# MAGI_sOLED.net
KiCad netlist of a schematic drawn in Altium Designer
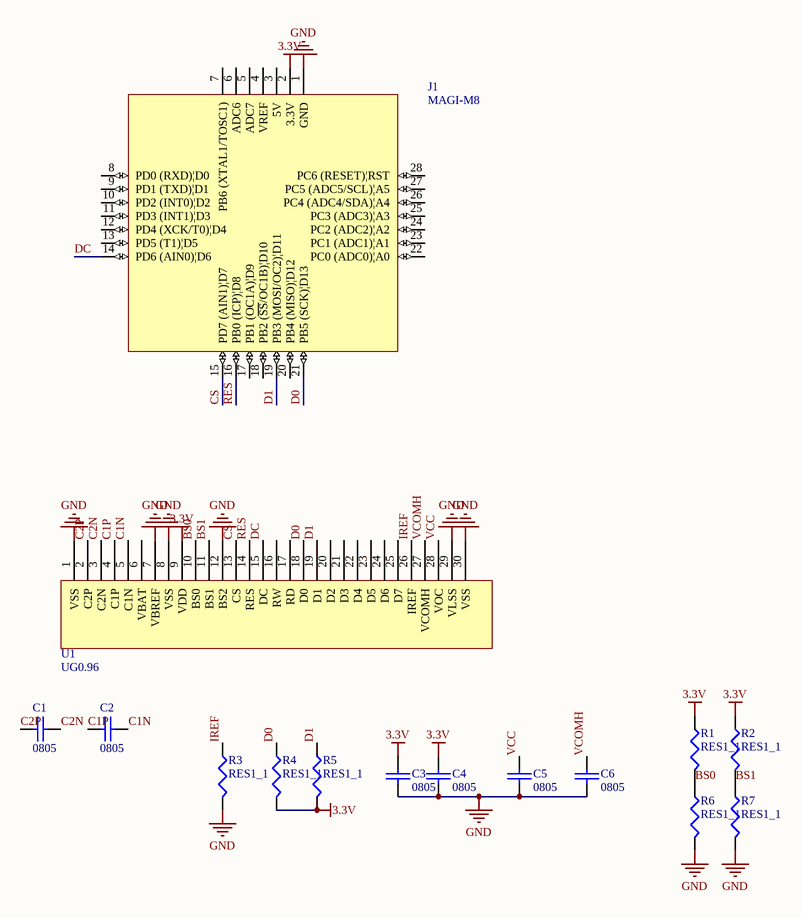
[diagram p0: MAGI'sOLED.SchDoc]

(export (version "E")
  (design (tool "Eeschema 10.0.6"))
  (components
    (comp (ref "C1")
      (value "0805")
      (footprint "6-0805_N")
      (description "Capacitor")
      (libsource (lib "电容器") (part "CAP_1"))
    )
    (comp (ref "C2")
      (value "0805")
      (footprint "6-0805_N")
      (description "Capacitor")
      (libsource (lib "电容器") (part "CAP_1"))
    )
    (comp (ref "C3")
      (value "0805")
      (footprint "6-0805_N")
      (description "Capacitor")
      (libsource (lib "电容器") (part "CAP_1"))
    )
    (comp (ref "C4")
      (value "0805")
      (footprint "6-0805_N")
      (description "Capacitor")
      (libsource (lib "电容器") (part "CAP_1"))
    )
    (comp (ref "C5")
      (value "0805")
      (footprint "6-0805_N")
      (description "Capacitor")
      (libsource (lib "电容器") (part "CAP_1"))
    )
    (comp (ref "C6")
      (value "0805")
      (footprint "6-0805_N")
      (description "Capacitor")
      (libsource (lib "电容器") (part "CAP_1"))
    )
    (comp (ref "J1") (value "MAGI-M8") (footprint "MAGI-M8") (libsource (lib "MAGI-M8") (part "MAGI-M8")))
    (comp (ref "R1") (value "RES1_1") (footprint "1608[0603]") (libsource (lib "电阻器") (part "RES1_1")))
    (comp (ref "R2") (value "RES1_1") (footprint "1608[0603]") (libsource (lib "电阻器") (part "RES1_1")))
    (comp (ref "R3") (value "RES1_1") (footprint "6-0805_n") (libsource (lib "电阻器") (part "RES1_1")))
    (comp (ref "R4") (value "RES1_1") (footprint "6-0805_n") (libsource (lib "电阻器") (part "RES1_1")))
    (comp (ref "R5") (value "RES1_1") (footprint "6-0805_n") (libsource (lib "电阻器") (part "RES1_1")))
    (comp (ref "R6") (value "RES1_1") (footprint "1608[0603]") (libsource (lib "电阻器") (part "RES1_1")))
    (comp (ref "R7") (value "RES1_1") (footprint "1608[0603]") (libsource (lib "电阻器") (part "RES1_1")))
    (comp (ref "U1") (value "UG0.96") (footprint "UG0.96") (libsource (lib "OLED") (part "UG0.96")))
  )
  (nets
    (net (code "1") (name "/BS0") (class "Default")
      (node (ref "R1") (pin "2") (pinfunction "2_2") (pintype "passive"))
      (node (ref "R6") (pin "1") (pinfunction "1_1") (pintype "passive"))
      (node (ref "U1") (pin "10") (pinfunction "BS0_10") (pintype "passive"))
    )
    (net (code "2") (name "/BS1") (class "Default")
      (node (ref "R2") (pin "2") (pinfunction "2_2") (pintype "passive"))
      (node (ref "R7") (pin "1") (pinfunction "1_1") (pintype "passive"))
      (node (ref "U1") (pin "11") (pinfunction "BS1_11") (pintype "passive"))
    )
    (net (code "3") (name "/C1N") (class "Default")
      (node (ref "C2") (pin "2") (pinfunction "2_2") (pintype "passive"))
      (node (ref "U1") (pin "5") (pinfunction "C1N_5") (pintype "passive"))
    )
    (net (code "4") (name "/C1P") (class "Default")
      (node (ref "C2") (pin "1") (pinfunction "1_1") (pintype "passive"))
      (node (ref "U1") (pin "4") (pinfunction "C1P_4") (pintype "passive"))
    )
    (net (code "5") (name "/C2N") (class "Default")
      (node (ref "C1") (pin "2") (pinfunction "2_2") (pintype "passive"))
      (node (ref "U1") (pin "3") (pinfunction "C2N_3") (pintype "passive"))
    )
    (net (code "6") (name "/C2P") (class "Default")
      (node (ref "C1") (pin "1") (pinfunction "1_1") (pintype "passive"))
      (node (ref "U1") (pin "2") (pinfunction "C2P_2") (pintype "passive"))
    )
    (net (code "7") (name "/CS") (class "Default")
      (node (ref "J1") (pin "15") (pinfunction "PD7_(AIN1)¦D7_15") (pintype "bidirectional"))
      (node (ref "U1") (pin "13") (pinfunction "CS_13") (pintype "passive"))
    )
    (net (code "8") (name "/D0") (class "Default")
      (node (ref "J1") (pin "21") (pinfunction "PB5_(SCK)¦D13_21") (pintype "bidirectional"))
      (node (ref "R4") (pin "1") (pinfunction "1_1") (pintype "passive"))
      (node (ref "U1") (pin "18") (pinfunction "D0_18") (pintype "passive"))
    )
    (net (code "9") (name "/D1") (class "Default")
      (node (ref "J1") (pin "19") (pinfunction "PB3_(MOSI/OC2)¦D11_19") (pintype "bidirectional"))
      (node (ref "R5") (pin "1") (pinfunction "1_1") (pintype "passive"))
      (node (ref "U1") (pin "19") (pinfunction "D1_19") (pintype "passive"))
    )
    (net (code "10") (name "/DC") (class "Default")
      (node (ref "J1") (pin "14") (pinfunction "PD6_(AIN0)¦D6_14") (pintype "bidirectional"))
      (node (ref "U1") (pin "15") (pinfunction "DC_15") (pintype "passive"))
    )
    (net (code "11") (name "/IREF") (class "Default")
      (node (ref "R3") (pin "1") (pinfunction "1_1") (pintype "passive"))
      (node (ref "U1") (pin "26") (pinfunction "IREF_26") (pintype "passive"))
    )
    (net (code "12") (name "/RES") (class "Default")
      (node (ref "J1") (pin "16") (pinfunction "PB0_(ICP)¦D8_16") (pintype "bidirectional"))
      (node (ref "U1") (pin "14") (pinfunction "RES_14") (pintype "passive"))
    )
    (net (code "13") (name "/VCC") (class "Default")
      (node (ref "C5") (pin "2") (pinfunction "2_2") (pintype "passive"))
      (node (ref "U1") (pin "28") (pinfunction "VOC_28") (pintype "passive"))
    )
    (net (code "14") (name "/VCOMH") (class "Default")
      (node (ref "C6") (pin "2") (pinfunction "2_2") (pintype "passive"))
      (node (ref "U1") (pin "27") (pinfunction "VCOMH_27") (pintype "passive"))
    )
    (net (code "15") (name "3.3V") (class "Default")
      (node (ref "C3") (pin "2") (pinfunction "2_2") (pintype "passive"))
      (node (ref "C4") (pin "2") (pinfunction "2_2") (pintype "passive"))
      (node (ref "J1") (pin "2") (pinfunction "3.3V_2") (pintype "power_in"))
      (node (ref "R1") (pin "1") (pinfunction "1_1") (pintype "passive"))
      (node (ref "R2") (pin "1") (pinfunction "1_1") (pintype "passive"))
      (node (ref "R4") (pin "2") (pinfunction "2_2") (pintype "passive"))
      (node (ref "R5") (pin "2") (pinfunction "2_2") (pintype "passive"))
      (node (ref "U1") (pin "9") (pinfunction "VDD_9") (pintype "passive"))
    )
    (net (code "16") (name "GND") (class "Default")
      (node (ref "C3") (pin "1") (pinfunction "1_1") (pintype "passive"))
      (node (ref "C4") (pin "1") (pinfunction "1_1") (pintype "passive"))
      (node (ref "C5") (pin "1") (pinfunction "1_1") (pintype "passive"))
      (node (ref "C6") (pin "1") (pinfunction "1_1") (pintype "passive"))
      (node (ref "J1") (pin "1") (pinfunction "GND_1") (pintype "power_in"))
      (node (ref "R3") (pin "2") (pinfunction "2_2") (pintype "passive"))
      (node (ref "R6") (pin "2") (pinfunction "2_2") (pintype "passive"))
      (node (ref "R7") (pin "2") (pinfunction "2_2") (pintype "passive"))
      (node (ref "U1") (pin "1") (pinfunction "VSS_1") (pintype "passive"))
      (node (ref "U1") (pin "12") (pinfunction "BS2_12") (pintype "passive"))
      (node (ref "U1") (pin "29") (pinfunction "VLSS_29") (pintype "passive"))
      (node (ref "U1") (pin "30") (pinfunction "VSS_30") (pintype "passive"))
      (node (ref "U1") (pin "7") (pinfunction "VBREF_7") (pintype "passive"))
      (node (ref "U1") (pin "8") (pinfunction "VSS_8") (pintype "passive"))
    )
    (net (code "17") (name "unconnected-(J1-5V-Pad3)") (class "Default")
      (node (ref "J1") (pin "3") (pinfunction "5V_3") (pintype "power_in"))
    )
    (net (code "18") (name "unconnected-(J1-ADC6-Pad6)") (class "Default")
      (node (ref "J1") (pin "6") (pinfunction "ADC6_6") (pintype "passive"))
    )
    (net (code "19") (name "unconnected-(J1-ADC7-Pad5)") (class "Default")
      (node (ref "J1") (pin "5") (pinfunction "ADC7_5") (pintype "passive"))
    )
    (net (code "20") (name "unconnected-(J1-PB1_(OC1A)¦D9-Pad17)") (class "Default")
      (node (ref "J1") (pin "17") (pinfunction "PB1_(OC1A)¦D9_17") (pintype "bidirectional"))
    )
    (net (code "21") (name "unconnected-(J1-PB2_(~{SS}{slash}OC1B)¦D10-Pad18)") (class "Default")
      (node (ref "J1") (pin "18") (pinfunction "PB2_(~{SS}/OC1B)¦D10_18") (pintype "bidirectional"))
    )
    (net (code "22") (name "unconnected-(J1-PB4_(MISO)¦D12-Pad20)") (class "Default")
      (node (ref "J1") (pin "20") (pinfunction "PB4_(MISO)¦D12_20") (pintype "bidirectional"))
    )
    (net (code "23") (name "unconnected-(J1-PB6_(XTAL1{slash}TOSC1)-Pad7)") (class "Default")
      (node (ref "J1") (pin "7") (pinfunction "PB6_(XTAL1/TOSC1)_7") (pintype "passive"))
    )
    (net (code "24") (name "unconnected-(J1-PC0_(ADC0)¦A0-Pad22)") (class "Default")
      (node (ref "J1") (pin "22") (pinfunction "PC0_(ADC0)¦A0_22") (pintype "bidirectional"))
    )
    (net (code "25") (name "unconnected-(J1-PC1_(ADC1)¦A1-Pad23)") (class "Default")
      (node (ref "J1") (pin "23") (pinfunction "PC1_(ADC1)¦A1_23") (pintype "bidirectional"))
    )
    (net (code "26") (name "unconnected-(J1-PC2_(ADC2)¦A2-Pad24)") (class "Default")
      (node (ref "J1") (pin "24") (pinfunction "PC2_(ADC2)¦A2_24") (pintype "bidirectional"))
    )
    (net (code "27") (name "unconnected-(J1-PC3_(ADC3)¦A3-Pad25)") (class "Default")
      (node (ref "J1") (pin "25") (pinfunction "PC3_(ADC3)¦A3_25") (pintype "bidirectional"))
    )
    (net (code "28") (name "unconnected-(J1-PC4_(ADC4{slash}SDA)¦A4-Pad26)") (class "Default")
      (node (ref "J1") (pin "26") (pinfunction "PC4_(ADC4/SDA)¦A4_26") (pintype "bidirectional"))
    )
    (net (code "29") (name "unconnected-(J1-PC5_(ADC5{slash}SCL)¦A5-Pad27)") (class "Default")
      (node (ref "J1") (pin "27") (pinfunction "PC5_(ADC5/SCL)¦A5_27") (pintype "bidirectional"))
    )
    (net (code "30") (name "unconnected-(J1-PC6_(RESET)¦RST-Pad28)") (class "Default")
      (node (ref "J1") (pin "28") (pinfunction "PC6_(RESET)¦RST_28") (pintype "bidirectional"))
    )
    (net (code "31") (name "unconnected-(J1-PD0_(RXD)¦D0-Pad8)") (class "Default")
      (node (ref "J1") (pin "8") (pinfunction "PD0_(RXD)¦D0_8") (pintype "bidirectional"))
    )
    (net (code "32") (name "unconnected-(J1-PD1_(TXD)¦D1-Pad9)") (class "Default")
      (node (ref "J1") (pin "9") (pinfunction "PD1_(TXD)¦D1_9") (pintype "bidirectional"))
    )
    (net (code "33") (name "unconnected-(J1-PD2_(INT0)¦D2-Pad10)") (class "Default")
      (node (ref "J1") (pin "10") (pinfunction "PD2_(INT0)¦D2_10") (pintype "bidirectional"))
    )
    (net (code "34") (name "unconnected-(J1-PD3_(INT1)¦D3-Pad11)") (class "Default")
      (node (ref "J1") (pin "11") (pinfunction "PD3_(INT1)¦D3_11") (pintype "bidirectional"))
    )
    (net (code "35") (name "unconnected-(J1-PD4_(XCK{slash}T0)¦D4-Pad12)") (class "Default")
      (node (ref "J1") (pin "12") (pinfunction "PD4_(XCK/T0)¦D4_12") (pintype "bidirectional"))
    )
    (net (code "36") (name "unconnected-(J1-PD5_(T1)¦D5-Pad13)") (class "Default")
      (node (ref "J1") (pin "13") (pinfunction "PD5_(T1)¦D5_13") (pintype "bidirectional"))
    )
    (net (code "37") (name "unconnected-(J1-VREF-Pad4)") (class "Default")
      (node (ref "J1") (pin "4") (pinfunction "VREF_4") (pintype "passive"))
    )
    (net (code "38") (name "unconnected-(U1-D2-Pad20)") (class "Default")
      (node (ref "U1") (pin "20") (pinfunction "D2_20") (pintype "passive"))
    )
    (net (code "39") (name "unconnected-(U1-D3-Pad21)") (class "Default")
      (node (ref "U1") (pin "21") (pinfunction "D3_21") (pintype "passive"))
    )
    (net (code "40") (name "unconnected-(U1-D4-Pad22)") (class "Default")
      (node (ref "U1") (pin "22") (pinfunction "D4_22") (pintype "passive"))
    )
    (net (code "41") (name "unconnected-(U1-D5-Pad23)") (class "Default")
      (node (ref "U1") (pin "23") (pinfunction "D5_23") (pintype "passive"))
    )
    (net (code "42") (name "unconnected-(U1-D6-Pad24)") (class "Default")
      (node (ref "U1") (pin "24") (pinfunction "D6_24") (pintype "passive"))
    )
    (net (code "43") (name "unconnected-(U1-D7-Pad25)") (class "Default")
      (node (ref "U1") (pin "25") (pinfunction "D7_25") (pintype "passive"))
    )
    (net (code "44") (name "unconnected-(U1-RD-Pad17)") (class "Default")
      (node (ref "U1") (pin "17") (pinfunction "RD_17") (pintype "passive"))
    )
    (net (code "45") (name "unconnected-(U1-RW-Pad16)") (class "Default")
      (node (ref "U1") (pin "16") (pinfunction "RW_16") (pintype "passive"))
    )
    (net (code "46") (name "unconnected-(U1-VBAT-Pad6)") (class "Default")
      (node (ref "U1") (pin "6") (pinfunction "VBAT_6") (pintype "passive"))
    )
  )
)
